# Sense_8_Signal_Isolation.net
KiCad netlist of a schematic drawn in Altium Designer
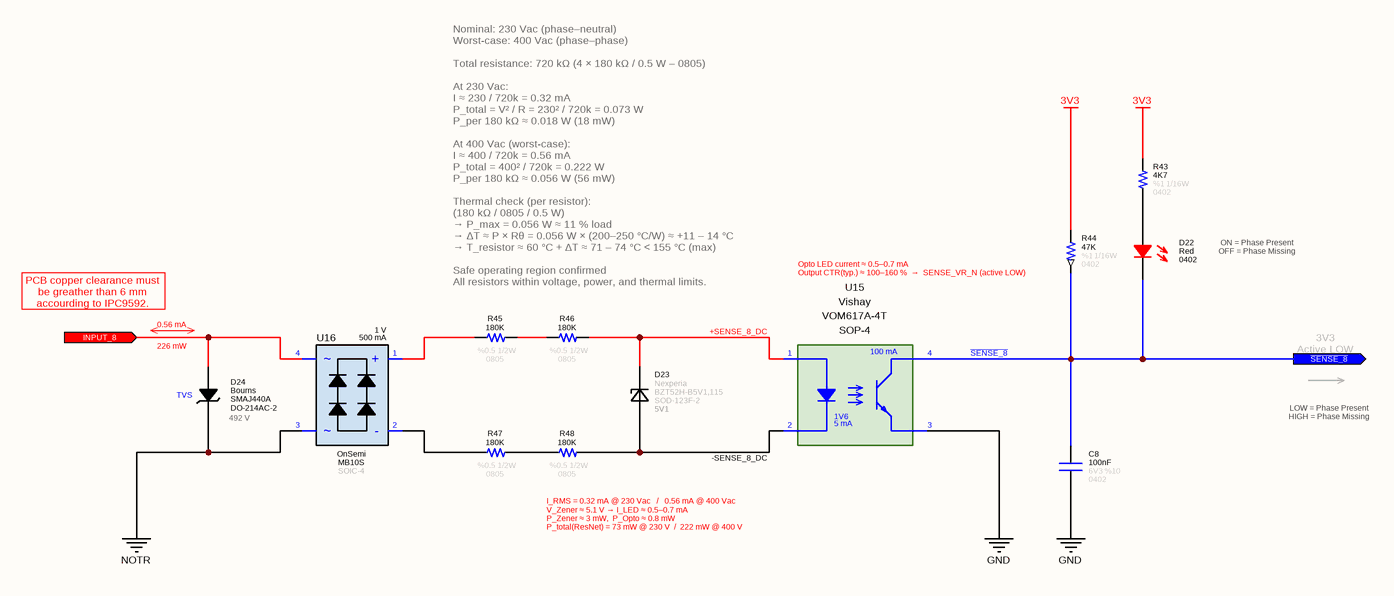
[diagram p0: Sense 8 Signal Isolation.SchDoc]

(export (version "E")
  (design (tool "Eeschema 10.0.6"))
  (components
    (comp (ref "C8")
      (value "100nF")
      (footprint "CAPACITOR_0402")
      (description "Capacitor (MLCC) - 100nF / 6V3 / 0402")
      (fields
        (field (name "MANUFACTURER PART NUMBER") "04026D104KAT4A")
        (field (name "TOLERANCE") "%10")
        (field (name "VOLTAGE") "6V3")
        (field (name "CASE") "0402")
        (field (name "Comment") "Capacitor - 100nF [0402] (MLCC)")
      )
      (libsource (lib "Akkoyun") (part "Capacitor - 100nF [0402-6V3]"))
    )
    (comp (ref "D22")
      (value "SMD LED (Red)")
      (footprint "LED_0402")
      (description "Standard LEDs - SMD MINI-MOLD ULTRA COMPACT RED")
      (fields
        (field (name "MANUFACTURER PART NUMBER") "SML-P12VTT86R")
        (field (name "CASE") "0402")
        (field (name "COLOR") "Red")
      )
      (libsource (lib "Akkoyun") (part "Diode - LED (0402-Red)"))
    )
    (comp (ref "D23")
      (value "BZT52H-B5V1,115")
      (footprint "SOD-123F-2")
      (description "Zener Diodes BZT52H-B5V1/SOD123F/SOD2")
      (fields
        (field (name "ZENER VOLTAGE") "5V1")
        (field (name "MANUFACTURER NAME") "Nexperia")
        (field (name "MANUFACTURER PART NUMBER") "BZT52H-B5V1,115")
        (field (name "CASE") "SOD-123F-2")
      )
      (libsource (lib "Akkoyun") (part "Diode - BZT52H-B5V1,115"))
    )
    (comp (ref "D24")
      (value "SMAJ440A")
      (footprint "DO-220AA-2")
      (description "ESD Protection Diodes / TVS Diodes 440volts 1uA .6 Amps Uni-Dir")
      (fields
        (field (name "BREAKDOWN VOLTAGE") "492 V")
        (field (name "MANUFACTURER NAME") "Bourns")
        (field (name "MANUFACTURER PART NUMBER") "SMAJ440A")
        (field (name "CASE") "DO-214AC-2")
      )
      (libsource (lib "Akkoyun") (part "Diode - SMAJ440A (TVS)"))
    )
    (comp (ref "R43")
      (value "4K7")
      (footprint "RESISTOR_0402")
      (description "Thick Film Resistors - SMD 1/16 W 4.7 KOhm 1%")
      (fields
        (field (name "MANUFACTURER PART NUMBER") "CRCW04024K70FKED")
        (field (name "TOLERANCE") "%1")
        (field (name "CASE") "0402")
        (field (name "POWER") "1/16W")
        (field (name "Comment") "4K7 - 0402 - %1 - 1/16W")
      )
      (libsource (lib "Akkoyun") (part "Resistor - 4K7 [0402]"))
    )
    (comp (ref "R44")
      (value "47K")
      (footprint "RESISTOR_0402")
      (description "Thick Film Resistors - SMD 1/16 W 47 KOhm 1%")
      (fields
        (field (name "MANUFACTURER PART NUMBER") "CRCW040247K0FKED")
        (field (name "TOLERANCE") "%1")
        (field (name "CASE") "0402")
        (field (name "POWER") "1/16W")
        (field (name "Comment") "47K - 0402 - %1 - 1/16W")
      )
      (libsource (lib "Akkoyun") (part "Resistor - 47K [0402]"))
    )
    (comp (ref "R45")
      (value "180K")
      (footprint "RESISTOR_0805")
      (description "Thick Film Resistors - SMD 0805 180Kohms 0.5W 0.5% AEC-Q200")
      (fields
        (field (name "MANUFACTURER PART NUMBER") "ERJ-P06D1803V")
        (field (name "TOLERANCE") "%0.5")
        (field (name "CASE") "0805")
        (field (name "POWER") "1/2W")
        (field (name "Comment") "180K - 0805 - %0.5 - 1/2W")
      )
      (libsource (lib "Akkoyun") (part "Resistor - 180K [0805]"))
    )
    (comp (ref "R46")
      (value "180K")
      (footprint "RESISTOR_0805")
      (description "Thick Film Resistors - SMD 0805 180Kohms 0.5W 0.5% AEC-Q200")
      (fields
        (field (name "MANUFACTURER PART NUMBER") "ERJ-P06D1803V")
        (field (name "TOLERANCE") "%0.5")
        (field (name "CASE") "0805")
        (field (name "POWER") "1/2W")
        (field (name "Comment") "180K - 0805 - %0.5 - 1/2W")
      )
      (libsource (lib "Akkoyun") (part "Resistor - 180K [0805]"))
    )
    (comp (ref "R47")
      (value "180K")
      (footprint "RESISTOR_0805")
      (description "Thick Film Resistors - SMD 0805 180Kohms 0.5W 0.5% AEC-Q200")
      (fields
        (field (name "MANUFACTURER PART NUMBER") "ERJ-P06D1803V")
        (field (name "TOLERANCE") "%0.5")
        (field (name "CASE") "0805")
        (field (name "POWER") "1/2W")
        (field (name "Comment") "180K - 0805 - %0.5 - 1/2W")
      )
      (libsource (lib "Akkoyun") (part "Resistor - 180K [0805]"))
    )
    (comp (ref "R48")
      (value "180K")
      (footprint "RESISTOR_0805")
      (description "Thick Film Resistors - SMD 0805 180Kohms 0.5W 0.5% AEC-Q200")
      (fields
        (field (name "MANUFACTURER PART NUMBER") "ERJ-P06D1803V")
        (field (name "TOLERANCE") "%0.5")
        (field (name "CASE") "0805")
        (field (name "POWER") "1/2W")
        (field (name "Comment") "180K - 0805 - %0.5 - 1/2W")
      )
      (libsource (lib "Akkoyun") (part "Resistor - 180K [0805]"))
    )
    (comp (ref "U15")
      (value "VOM617A-4T")
      (footprint "SOP-4V2")
      (description "Transistor Output Optocouplers Phototransistor Out CTR 160-320% 5mA")
      (fields
        (field (name "MANUFACTURER PART NUMBER") "VOM617A-4T")
        (field (name "MANUFACTURER NAME") "Vishay")
        (field (name "CASE") "SOP-4")
        (field (name "IF - FORWARD CURRENT") "5 mA")
        (field (name "VF - FORWARD VOLTAGE") "1V6")
        (field (name "MAXIMUM COLLECTOR CURRENT") "100 mA")
      )
      (libsource (lib "Akkoyun") (part "IC - VOM617A"))
    )
    (comp (ref "U16")
      (value "LTV-846S")
      (footprint "SOIC-4")
      (description "Transistor Output Optocouplers Optocplr Phototrans 4-Channel")
      (fields
        (field (name "IF - FORWARD CURRENT") "500 mA")
        (field (name "VF - FORWARD VOLTAGE") "1 V")
        (field (name "MANUFACTURER NAME") "OnSemi")
        (field (name "MANUFACTURER PART NUMBER") "MB10S")
        (field (name "CASE") "SOIC-4")
      )
      (libsource (lib "Akkoyun") (part "IC - MB10S"))
    )
  )
  (nets
    (net (code "1") (name "/+SENSE_8_DC") (class "Default")
      (node (ref "D23") (pin "1") (pinfunction "Cathode_1") (pintype "passive"))
      (node (ref "R46") (pin "1") (pinfunction "1_1") (pintype "passive"))
      (node (ref "U15") (pin "1") (pinfunction "LED_Anode_1") (pintype "passive"))
    )
    (net (code "2") (name "/-SENSE_8_DC") (class "Default")
      (node (ref "D23") (pin "2") (pinfunction "Anode_2") (pintype "passive"))
      (node (ref "R48") (pin "1") (pinfunction "1_1") (pintype "passive"))
      (node (ref "U15") (pin "2") (pinfunction "LED_Cathode_2") (pintype "passive"))
    )
    (net (code "3") (name "/INPUT_8") (class "Default")
      (node (ref "D24") (pin "1") (pinfunction "Anode_1") (pintype "passive"))
      (node (ref "U16") (pin "4") (pinfunction "~_4") (pintype "passive"))
    )
    (net (code "4") (name "/~{SENSE_8}") (class "Default")
      (node (ref "C8") (pin "2") (pinfunction "2_2") (pintype "passive"))
      (node (ref "D22") (pin "1") (pinfunction "1_1") (pintype "passive"))
      (node (ref "R44") (pin "1") (pinfunction "1_1") (pintype "output"))
      (node (ref "U15") (pin "4") (pinfunction "Collector_4") (pintype "passive"))
    )
    (net (code "5") (name "3V3") (class "Default")
      (node (ref "R43") (pin "2") (pinfunction "2_2") (pintype "passive"))
      (node (ref "R44") (pin "2") (pinfunction "2_2") (pintype "passive"))
    )
    (net (code "6") (name "GND") (class "Default")
      (node (ref "C8") (pin "1") (pinfunction "1_1") (pintype "passive"))
      (node (ref "U15") (pin "3") (pinfunction "Emiter_3") (pintype "passive"))
    )
    (net (code "7") (name "NOTR") (class "Default")
      (node (ref "D24") (pin "2") (pinfunction "Cathode_2") (pintype "passive"))
      (node (ref "U16") (pin "3") (pinfunction "~_3") (pintype "passive"))
    )
    (net (code "8") (name "Net-(D22-Pad2)") (class "Default")
      (node (ref "D22") (pin "2") (pinfunction "2_2") (pintype "passive"))
      (node (ref "R43") (pin "1") (pinfunction "1_1") (pintype "passive"))
    )
    (net (code "9") (name "Net-(R45-Pad1)") (class "Default")
      (node (ref "R45") (pin "1") (pinfunction "1_1") (pintype "passive"))
      (node (ref "R46") (pin "2") (pinfunction "2_2") (pintype "passive"))
    )
    (net (code "10") (name "Net-(R47-Pad1)") (class "Default")
      (node (ref "R47") (pin "1") (pinfunction "1_1") (pintype "passive"))
      (node (ref "R48") (pin "2") (pinfunction "2_2") (pintype "passive"))
    )
    (net (code "11") (name "Net-(U16-+)") (class "Default")
      (node (ref "R45") (pin "2") (pinfunction "2_2") (pintype "passive"))
      (node (ref "U16") (pin "1") (pinfunction "+_1") (pintype "passive"))
    )
    (net (code "12") (name "Net-(U16--)") (class "Default")
      (node (ref "R47") (pin "2") (pinfunction "2_2") (pintype "passive"))
      (node (ref "U16") (pin "2") (pinfunction "-_2") (pintype "passive"))
    )
  )
)
